# a.net
KiCad netlist of a schematic drawn in EAGLE
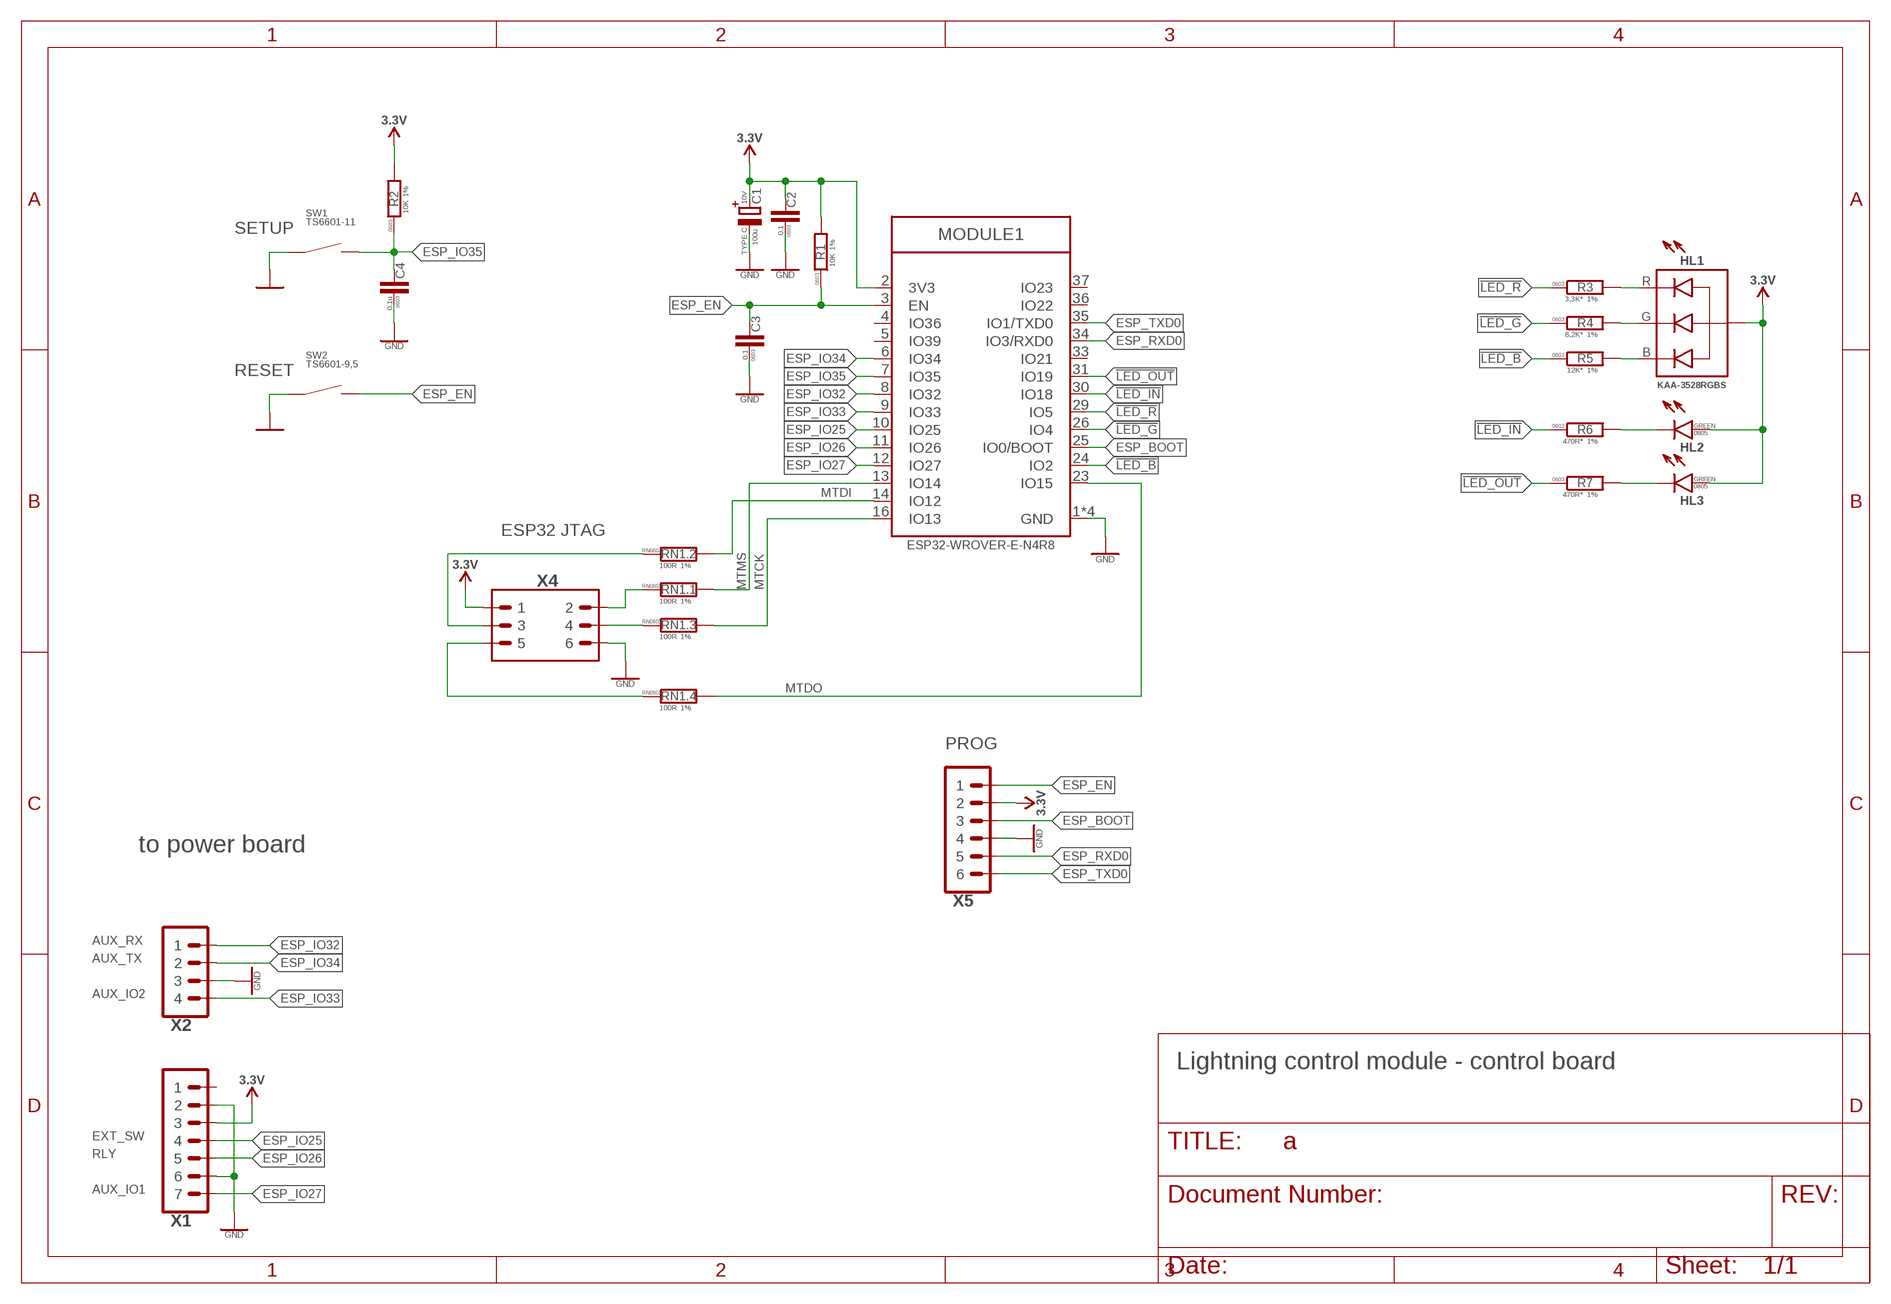
[diagram p0: schematic, sheet 1]

(export (version "E")
  (design (tool "Eeschema 10.0.6"))
  (components
    (comp (ref "C1")
      (value "100u")
      (footprint "eagle-import:CTANT_TYPE_C")
      (fields (field (name "PACKAGE") "TYPE C") (field (name "VOLTAGE") "10V"))
      (libsource (lib "eagle-import") (part "CPOL-TANT-TYPE-C"))
    )
    (comp (ref "C2")
      (value "0.1")
      (footprint "eagle-import:C0603")
      (fields (field (name "PACKAGE") "0603"))
      (libsource (lib "eagle-import") (part "C-0603"))
    )
    (comp (ref "C3")
      (value "0.1")
      (footprint "eagle-import:C0603")
      (fields (field (name "PACKAGE") "0603"))
      (libsource (lib "eagle-import") (part "C-0603"))
    )
    (comp (ref "C4")
      (value "0.1u")
      (footprint "eagle-import:C0603")
      (fields (field (name "PACKAGE") "0603"))
      (libsource (lib "eagle-import") (part "C-0603"))
    )
    (comp (ref "HL1")
      (value "LED_RGB-KAA-3528RGBS")
      (footprint "eagle-import:LED3528")
      (fields (field (name "MANF") "Kingbright") (field (name "MANF#") "KAA-3528RGBS"))
      (libsource (lib "eagle-import") (part "LED_RGB-KAA-3528RGBS"))
    )
    (comp (ref "HL2")
      (value "LED-0805")
      (footprint "eagle-import:LED0805")
      (fields (field (name "PACKAGE") "0805") (field (name "COLOR") "GREEN"))
      (libsource (lib "eagle-import") (part "LED-0805"))
    )
    (comp (ref "HL3")
      (value "LED-0805")
      (footprint "eagle-import:LED0805")
      (fields (field (name "PACKAGE") "0805") (field (name "COLOR") "GREEN"))
      (libsource (lib "eagle-import") (part "LED-0805"))
    )
    (comp (ref "MODULE1")
      (value "ESP32-WROVER-(I)E")
      (footprint "eagle-import:ESP32-WROVER-E")
      (fields (field (name "MANF#") "ESP32-WROVER-E-N4R8") (field (name "MANF") "Espressif Systems"))
      (libsource (lib "eagle-import") (part "ESP32-WROVER-(I)E"))
    )
    (comp (ref "R1")
      (value "10K")
      (footprint "eagle-import:R0603")
      (fields (field (name "PACKAGE") "0603") (field (name "TOLERANCE") "1%"))
      (libsource (lib "eagle-import") (part "R-0603-1%"))
    )
    (comp (ref "R2")
      (value "10K")
      (footprint "eagle-import:R0603")
      (fields (field (name "PACKAGE") "0603") (field (name "TOLERANCE") "1%"))
      (libsource (lib "eagle-import") (part "R-0603-1%"))
    )
    (comp (ref "R3")
      (value "3,3K*")
      (footprint "eagle-import:R0603")
      (fields (field (name "PACKAGE") "0603") (field (name "TOLERANCE") "1%"))
      (libsource (lib "eagle-import") (part "R-0603-1%"))
    )
    (comp (ref "R4")
      (value "8,2K*")
      (footprint "eagle-import:R0603")
      (fields (field (name "PACKAGE") "0603") (field (name "TOLERANCE") "1%"))
      (libsource (lib "eagle-import") (part "R-0603-1%"))
    )
    (comp (ref "R5")
      (value "12K*")
      (footprint "eagle-import:R0603")
      (fields (field (name "PACKAGE") "0603") (field (name "TOLERANCE") "1%"))
      (libsource (lib "eagle-import") (part "R-0603-1%"))
    )
    (comp (ref "R6")
      (value "470R*")
      (footprint "eagle-import:R0603")
      (fields (field (name "PACKAGE") "0603") (field (name "TOLERANCE") "1%"))
      (libsource (lib "eagle-import") (part "R-0603-1%"))
    )
    (comp (ref "R7")
      (value "470R*")
      (footprint "eagle-import:R0603")
      (fields (field (name "PACKAGE") "0603") (field (name "TOLERANCE") "1%"))
      (libsource (lib "eagle-import") (part "R-0603-1%"))
    )
    (comp (ref "RN1")
      (value "100R")
      (footprint "eagle-import:R_4X0603")
      (fields (field (name "PACKAGE") "RN0603") (field (name "TOLERANCE") "1%"))
      (libsource (lib "eagle-import") (part "RN-0603-1%"))
    )
    (comp (ref "SW1")
      (value "TS6601-11")
      (footprint "eagle-import:SW4-6.0X6.0X5.0MM")
      (fields (field (name "MANF") "KLS"))
      (libsource (lib "eagle-import") (part "TACT_SWITCH-6X6-PTH"))
    )
    (comp (ref "SW2")
      (value "TS6601-9,5")
      (footprint "eagle-import:SW4-6.0X6.0X5.0MM")
      (fields (field (name "MANF") "KLS"))
      (libsource (lib "eagle-import") (part "TACT_SWITCH-6X6-PTH"))
    )
    (comp (ref "X1")
      (value "PINHEAD_1X07-2.54")
      (footprint "eagle-import:1X07-PTH-2.54")
      (libsource (lib "eagle-import") (part "PINHEAD_1X07-2.54"))
    )
    (comp (ref "X2")
      (value "PINHEAD_1X04-2.54")
      (footprint "eagle-import:1X04-PTH-2.54")
      (libsource (lib "eagle-import") (part "PINHEAD_1X04-2.54"))
    )
    (comp (ref "X4")
      (value "PINHEAD_2X03-PTH-2.54")
      (footprint "eagle-import:2X03-PTH-2.54")
      (libsource (lib "eagle-import") (part "PINHEAD_2X03-PTH-2.54"))
    )
    (comp (ref "X5")
      (value "PINHEAD_1X06-2-MALE")
      (footprint "eagle-import:1X06-PTH-2")
      (libsource (lib "eagle-import") (part "PINHEAD_1X06-2-MALE"))
    )
  )
  (nets
    (net (code "1") (name "/MTCK") (class "Default")
      (node (ref "MODULE1") (pin "16") (pinfunction "IO13_16") (pintype "tri_state"))
      (node (ref "RN1") (pin "6") (pinfunction "2_6") (pintype "passive"))
    )
    (net (code "2") (name "/MTDI") (class "Default")
      (node (ref "MODULE1") (pin "14") (pinfunction "IO12_14") (pintype "tri_state"))
      (node (ref "RN1") (pin "7") (pinfunction "2_7") (pintype "passive"))
    )
    (net (code "3") (name "/MTDO") (class "Default")
      (node (ref "MODULE1") (pin "23") (pinfunction "IO15_23") (pintype "tri_state"))
      (node (ref "RN1") (pin "5") (pinfunction "2_5") (pintype "passive"))
    )
    (net (code "4") (name "/MTMS") (class "Default")
      (node (ref "MODULE1") (pin "13") (pinfunction "IO14_13") (pintype "tri_state"))
      (node (ref "RN1") (pin "8") (pinfunction "2_8") (pintype "passive"))
    )
    (net (code "5") (name "/~{LED_B}") (class "Default")
      (node (ref "MODULE1") (pin "24") (pinfunction "IO2_24") (pintype "tri_state"))
      (node (ref "R5") (pin "1") (pinfunction "1_1") (pintype "passive"))
    )
    (net (code "6") (name "/~{LED_G}") (class "Default")
      (node (ref "MODULE1") (pin "26") (pinfunction "IO4_26") (pintype "tri_state"))
      (node (ref "R4") (pin "1") (pinfunction "1_1") (pintype "passive"))
    )
    (net (code "7") (name "/~{LED_IN}") (class "Default")
      (node (ref "MODULE1") (pin "30") (pinfunction "IO18_30") (pintype "tri_state"))
      (node (ref "R6") (pin "1") (pinfunction "1_1") (pintype "passive"))
    )
    (net (code "8") (name "/~{LED_OUT}") (class "Default")
      (node (ref "MODULE1") (pin "31") (pinfunction "IO19_31") (pintype "tri_state"))
      (node (ref "R7") (pin "1") (pinfunction "1_1") (pintype "passive"))
    )
    (net (code "9") (name "/~{LED_R}") (class "Default")
      (node (ref "MODULE1") (pin "29") (pinfunction "IO5_29") (pintype "tri_state"))
      (node (ref "R3") (pin "1") (pinfunction "1_1") (pintype "passive"))
    )
    (net (code "10") (name "3.3V") (class "Default")
      (node (ref "C1") (pin "+") (pinfunction "+_+") (pintype "passive"))
      (node (ref "C2") (pin "2") (pinfunction "2_2") (pintype "passive"))
      (node (ref "HL1") (pin "2") (pinfunction "A_2") (pintype "bidirectional"))
      (node (ref "HL2") (pin "A") (pinfunction "A_A") (pintype "bidirectional"))
      (node (ref "HL3") (pin "A") (pinfunction "A_A") (pintype "bidirectional"))
      (node (ref "MODULE1") (pin "2") (pinfunction "3V3_2") (pintype "passive"))
      (node (ref "R1") (pin "2") (pinfunction "2_2") (pintype "passive"))
      (node (ref "R2") (pin "2") (pinfunction "2_2") (pintype "passive"))
      (node (ref "X1") (pin "3") (pinfunction "3_3") (pintype "passive"))
      (node (ref "X4") (pin "1") (pinfunction "1_1") (pintype "passive"))
      (node (ref "X5") (pin "2") (pinfunction "2_2") (pintype "passive"))
    )
    (net (code "11") (name "ESP_BOOT") (class "Default")
      (node (ref "MODULE1") (pin "25") (pinfunction "IO0/BOOT_25") (pintype "tri_state"))
      (node (ref "X5") (pin "3") (pinfunction "3_3") (pintype "passive"))
    )
    (net (code "12") (name "ESP_EN") (class "Default")
      (node (ref "C3") (pin "2") (pinfunction "2_2") (pintype "passive"))
      (node (ref "MODULE1") (pin "3") (pinfunction "EN_3") (pintype "tri_state"))
      (node (ref "R1") (pin "1") (pinfunction "1_1") (pintype "passive"))
      (node (ref "SW2") (pin "2") (pinfunction "2_2") (pintype "bidirectional"))
      (node (ref "SW2") (pin "3") (pinfunction "2_3") (pintype "bidirectional"))
      (node (ref "X5") (pin "1") (pinfunction "1_1") (pintype "passive"))
    )
    (net (code "13") (name "ESP_IO25") (class "Default")
      (node (ref "MODULE1") (pin "10") (pinfunction "IO25_10") (pintype "tri_state"))
      (node (ref "X1") (pin "4") (pinfunction "4_4") (pintype "passive"))
    )
    (net (code "14") (name "ESP_IO26") (class "Default")
      (node (ref "MODULE1") (pin "11") (pinfunction "IO26_11") (pintype "tri_state"))
      (node (ref "X1") (pin "5") (pinfunction "5_5") (pintype "passive"))
    )
    (net (code "15") (name "ESP_IO27") (class "Default")
      (node (ref "MODULE1") (pin "12") (pinfunction "IO27_12") (pintype "tri_state"))
      (node (ref "X1") (pin "7") (pinfunction "7_7") (pintype "passive"))
    )
    (net (code "16") (name "ESP_IO32") (class "Default")
      (node (ref "MODULE1") (pin "8") (pinfunction "IO32_8") (pintype "tri_state"))
      (node (ref "X2") (pin "1") (pinfunction "1_1") (pintype "passive"))
    )
    (net (code "17") (name "ESP_IO33") (class "Default")
      (node (ref "MODULE1") (pin "9") (pinfunction "IO33_9") (pintype "tri_state"))
      (node (ref "X2") (pin "4") (pinfunction "4_4") (pintype "passive"))
    )
    (net (code "18") (name "ESP_IO34") (class "Default")
      (node (ref "MODULE1") (pin "6") (pinfunction "IO34_6") (pintype "tri_state"))
      (node (ref "X2") (pin "2") (pinfunction "2_2") (pintype "passive"))
    )
    (net (code "19") (name "ESP_IO35") (class "Default")
      (node (ref "C4") (pin "2") (pinfunction "2_2") (pintype "passive"))
      (node (ref "MODULE1") (pin "7") (pinfunction "IO35_7") (pintype "tri_state"))
      (node (ref "R2") (pin "1") (pinfunction "1_1") (pintype "passive"))
      (node (ref "SW1") (pin "2") (pinfunction "2_2") (pintype "bidirectional"))
      (node (ref "SW1") (pin "3") (pinfunction "2_3") (pintype "bidirectional"))
    )
    (net (code "20") (name "ESP_RXD0") (class "Default")
      (node (ref "MODULE1") (pin "34") (pinfunction "IO3/RXD0_34") (pintype "tri_state"))
      (node (ref "X5") (pin "5") (pinfunction "5_5") (pintype "passive"))
    )
    (net (code "21") (name "ESP_TXD0") (class "Default")
      (node (ref "MODULE1") (pin "35") (pinfunction "IO1/TXD0_35") (pintype "tri_state"))
      (node (ref "X5") (pin "6") (pinfunction "6_6") (pintype "passive"))
    )
    (net (code "22") (name "GND") (class "Default")
      (node (ref "C1") (pin "-") (pinfunction "-_-") (pintype "passive"))
      (node (ref "C2") (pin "1") (pinfunction "1_1") (pintype "passive"))
      (node (ref "C3") (pin "1") (pinfunction "1_1") (pintype "passive"))
      (node (ref "C4") (pin "1") (pinfunction "1_1") (pintype "passive"))
      (node (ref "MODULE1") (pin "1") (pinfunction "GND_1") (pintype "tri_state"))
      (node (ref "MODULE1") (pin "15") (pinfunction "GND_15") (pintype "tri_state"))
      (node (ref "MODULE1") (pin "38") (pinfunction "GND_38") (pintype "tri_state"))
      (node (ref "MODULE1") (pin "39") (pinfunction "GND_39") (pintype "tri_state"))
      (node (ref "SW1") (pin "1") (pinfunction "1_1") (pintype "bidirectional"))
      (node (ref "SW1") (pin "4") (pinfunction "1_4") (pintype "bidirectional"))
      (node (ref "SW2") (pin "1") (pinfunction "1_1") (pintype "bidirectional"))
      (node (ref "SW2") (pin "4") (pinfunction "1_4") (pintype "bidirectional"))
      (node (ref "X1") (pin "2") (pinfunction "2_2") (pintype "passive"))
      (node (ref "X1") (pin "6") (pinfunction "6_6") (pintype "passive"))
      (node (ref "X2") (pin "3") (pinfunction "3_3") (pintype "passive"))
      (node (ref "X4") (pin "6") (pinfunction "6_6") (pintype "passive"))
      (node (ref "X5") (pin "4") (pinfunction "4_4") (pintype "passive"))
    )
    (net (code "23") (name "Net-(HL1-B)") (class "Default")
      (node (ref "HL1") (pin "4") (pinfunction "B_4") (pintype "bidirectional"))
      (node (ref "R5") (pin "2") (pinfunction "2_2") (pintype "passive"))
    )
    (net (code "24") (name "Net-(HL1-G)") (class "Default")
      (node (ref "HL1") (pin "3") (pinfunction "G_3") (pintype "bidirectional"))
      (node (ref "R4") (pin "2") (pinfunction "2_2") (pintype "passive"))
    )
    (net (code "25") (name "Net-(HL1-R)") (class "Default")
      (node (ref "HL1") (pin "1") (pinfunction "R_1") (pintype "bidirectional"))
      (node (ref "R3") (pin "2") (pinfunction "2_2") (pintype "passive"))
    )
    (net (code "26") (name "Net-(HL2-PadC)") (class "Default")
      (node (ref "HL2") (pin "C") (pinfunction "C_C") (pintype "bidirectional"))
      (node (ref "R6") (pin "2") (pinfunction "2_2") (pintype "passive"))
    )
    (net (code "27") (name "Net-(HL3-PadC)") (class "Default")
      (node (ref "HL3") (pin "C") (pinfunction "C_C") (pintype "bidirectional"))
      (node (ref "R7") (pin "2") (pinfunction "2_2") (pintype "passive"))
    )
    (net (code "28") (name "Net-(RN1-Pad1)") (class "Default")
      (node (ref "RN1") (pin "1") (pinfunction "1_1") (pintype "passive"))
      (node (ref "X4") (pin "2") (pinfunction "2_2") (pintype "passive"))
    )
    (net (code "29") (name "Net-(RN1B-1)") (class "Default")
      (node (ref "RN1") (pin "2") (pinfunction "1_2") (pintype "passive"))
      (node (ref "X4") (pin "3") (pinfunction "3_3") (pintype "passive"))
    )
    (net (code "30") (name "Net-(RN1C-1)") (class "Default")
      (node (ref "RN1") (pin "3") (pinfunction "1_3") (pintype "passive"))
      (node (ref "X4") (pin "4") (pinfunction "4_4") (pintype "passive"))
    )
    (net (code "31") (name "Net-(RN1D-1)") (class "Default")
      (node (ref "RN1") (pin "4") (pinfunction "1_4") (pintype "passive"))
      (node (ref "X4") (pin "5") (pinfunction "5_5") (pintype "passive"))
    )
    (net (code "32") (name "unconnected-(MODULE1-IO21-Pad33)") (class "Default")
      (node (ref "MODULE1") (pin "33") (pinfunction "IO21_33") (pintype "tri_state"))
    )
    (net (code "33") (name "unconnected-(MODULE1-IO22-Pad36)") (class "Default")
      (node (ref "MODULE1") (pin "36") (pinfunction "IO22_36") (pintype "tri_state"))
    )
    (net (code "34") (name "unconnected-(MODULE1-IO23-Pad37)") (class "Default")
      (node (ref "MODULE1") (pin "37") (pinfunction "IO23_37") (pintype "tri_state"))
    )
    (net (code "35") (name "unconnected-(MODULE1-IO36-Pad4)") (class "Default")
      (node (ref "MODULE1") (pin "4") (pinfunction "IO36_4") (pintype "tri_state"))
    )
    (net (code "36") (name "unconnected-(MODULE1-IO39-Pad5)") (class "Default")
      (node (ref "MODULE1") (pin "5") (pinfunction "IO39_5") (pintype "tri_state"))
    )
    (net (code "37") (name "unconnected-(X1-Pad1)") (class "Default")
      (node (ref "X1") (pin "1") (pinfunction "1_1") (pintype "passive"))
    )
  )
)
